# VolCon_ENC.net
KiCad netlist of a schematic drawn in EAGLE
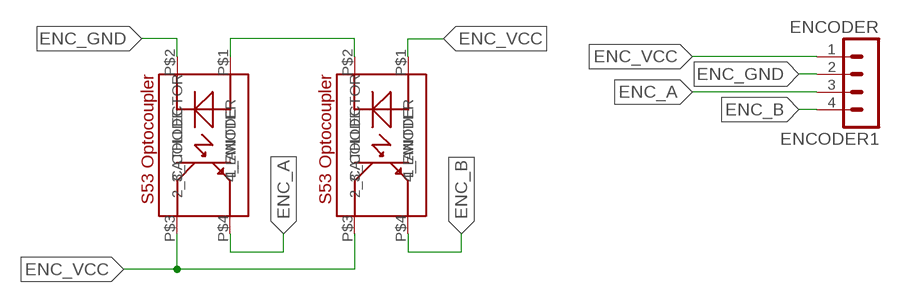
[diagram p0: schematic, sheet 1]

(export (version "E")
  (design (tool "Eeschema 10.0.6"))
  (components
    (comp (ref "ENCODER1")
      (value "ENCODER")
      (footprint "eagle-import:MA04-1")
      (libsource (lib "eagle-import") (part "MA04-1"))
    )
    (comp (ref "U$3")
      (value "SHARP_S53")
      (footprint "eagle-import:SHARP_S53")
      (libsource (lib "eagle-import") (part "SHARP_S53"))
    )
    (comp (ref "U$4")
      (value "SHARP_S53")
      (footprint "eagle-import:SHARP_S53")
      (libsource (lib "eagle-import") (part "SHARP_S53"))
    )
  )
  (nets
    (net (code "1") (name "ENC_A") (class "Default")
      (node (ref "ENCODER1") (pin "3") (pinfunction "3_3") (pintype "passive"))
      (node (ref "U$4") (pin "P$4") (pinfunction "4_EMITTER_P$4") (pintype "bidirectional"))
    )
    (net (code "2") (name "ENC_B") (class "Default")
      (node (ref "ENCODER1") (pin "4") (pinfunction "4_4") (pintype "passive"))
      (node (ref "U$3") (pin "P$4") (pinfunction "4_EMITTER_P$4") (pintype "bidirectional"))
    )
    (net (code "3") (name "ENC_GND") (class "Default")
      (node (ref "ENCODER1") (pin "2") (pinfunction "2_2") (pintype "passive"))
      (node (ref "U$4") (pin "P$2") (pinfunction "2_CATHODE_P$2") (pintype "bidirectional"))
    )
    (net (code "4") (name "ENC_VCC") (class "Default")
      (node (ref "ENCODER1") (pin "1") (pinfunction "1_1") (pintype "passive"))
      (node (ref "U$3") (pin "P$1") (pinfunction "1_ANODE_P$1") (pintype "bidirectional"))
      (node (ref "U$3") (pin "P$3") (pinfunction "3_COLLECTOR_P$3") (pintype "bidirectional"))
      (node (ref "U$4") (pin "P$3") (pinfunction "3_COLLECTOR_P$3") (pintype "bidirectional"))
    )
    (net (code "5") (name "Net-(U$3-2_CATHODE)") (class "Default")
      (node (ref "U$3") (pin "P$2") (pinfunction "2_CATHODE_P$2") (pintype "bidirectional"))
      (node (ref "U$4") (pin "P$1") (pinfunction "1_ANODE_P$1") (pintype "bidirectional"))
    )
  )
)
